# LEDBAKL_TPS61040DRV.net
KiCad netlist of a schematic drawn in Altium Designer
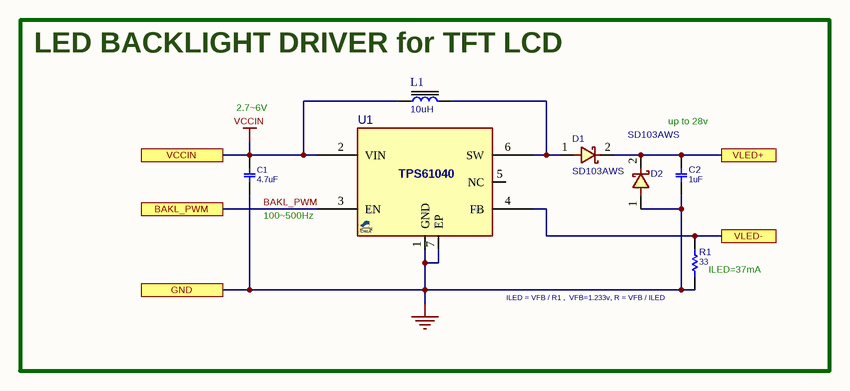
[diagram p0: LEDBAKL_TPS61040DRV.SchDoc]

(export (version "E")
  (design (tool "Eeschema 10.0.6"))
  (components
    (comp (ref "C1")
      (value "4.7uF")
      (footprint "C0402")
      (description "CAP, MLCC")
      (fields (field (name "MANF_P#") "CL05A475MP5NRNC") (field (name "MANF") "Samsung"))
      (libsource (lib "passive_smd") (part "CAP_SMD_MLCC"))
    )
    (comp (ref "C2")
      (value "1uF")
      (footprint "C0603")
      (description "CAP, MLCC")
      (fields (field (name "MANF_P#") "CL10A105KB8NNNC") (field (name "MANF") "Samsung"))
      (libsource (lib "passive_smd") (part "CAP_SMD_MLCC"))
    )
    (comp (ref "D1")
      (value "SD103AWS")
      (footprint "D_SOD323")
      (description "DIODE, SCHOTTKY, 40V, 2A")
      (fields (field (name "MANF") "DIODES"))
      (libsource (lib "diode") (part "DIODE_SMD_SCHOTTKY_1N5819"))
    )
    (comp (ref "D2")
      (value "SD103AWS")
      (footprint "D_SOD323")
      (description "DIODE, SCHOTTKY, 40V, 2A")
      (fields (field (name "MANF") "DIODES"))
      (libsource (lib "diode") (part "DIODE_SMD_SCHOTTKY_1N5819"))
    )
    (comp (ref "L1")
      (value "10uH")
      (footprint "L_4")
      (description "INDUCTOR, POWER, SMD")
      (fields (field (name "MANF_P#") "GCD43-100MC"))
      (libsource (lib "passive") (part "INDPWR_SMD"))
    )
    (comp (ref "R1")
      (value "33")
      (footprint "R0402")
      (description "RESISTOR, SMD, 20K, 0402")
      (fields (field (name "MANF") "Yageo") (field (name "MANF_P#") "RK73H1ETTP2002F"))
      (libsource (lib "chila_passive") (part "RES_SMD"))
    )
    (comp (ref "U1")
      (value "TPS61040")
      (footprint "SON65_6T_2020")
      (description "REG, Switching, Boost, 0.4A, ADJ, 1MHz, SOT-23-5")
      (fields (field (name "MANF_P#") "TPS61040DRV") (field (name "MANF") "TI"))
      (libsource (lib "pwr_switching_boost") (part "VREG_TPS61040_SON6"))
    )
  )
  (nets
    (net (code "1") (name "/BAKL_PWM") (class "Default")
      (node (ref "U1") (pin "3") (pinfunction "EN_3") (pintype "passive"))
    )
    (net (code "2") (name "/VLED+") (class "Default")
      (node (ref "C2") (pin "2") (pinfunction "2_2") (pintype "passive"))
      (node (ref "D1") (pin "2") (pinfunction "2_2") (pintype "passive"))
      (node (ref "D2") (pin "2") (pinfunction "2_2") (pintype "passive"))
    )
    (net (code "3") (name "/VLED-") (class "Default")
      (node (ref "R1") (pin "1") (pinfunction "1_1") (pintype "passive"))
      (node (ref "U1") (pin "4") (pinfunction "FB_4") (pintype "passive"))
    )
    (net (code "4") (name "GND") (class "Default")
      (node (ref "C1") (pin "1") (pinfunction "1_1") (pintype "passive"))
      (node (ref "C2") (pin "1") (pinfunction "1_1") (pintype "passive"))
      (node (ref "D2") (pin "1") (pinfunction "1_1") (pintype "passive"))
      (node (ref "R1") (pin "2") (pinfunction "2_2") (pintype "passive"))
      (node (ref "U1") (pin "1") (pinfunction "GND_1") (pintype "passive"))
      (node (ref "U1") (pin "7") (pinfunction "EP_7") (pintype "passive"))
    )
    (net (code "5") (name "Net-(U1-SW)") (class "Default")
      (node (ref "D1") (pin "1") (pinfunction "1_1") (pintype "passive"))
      (node (ref "L1") (pin "2") (pinfunction "2_2") (pintype "passive"))
      (node (ref "U1") (pin "6") (pinfunction "SW_6") (pintype "passive"))
    )
    (net (code "6") (name "VCCIN") (class "Default")
      (node (ref "C1") (pin "2") (pinfunction "2_2") (pintype "passive"))
      (node (ref "L1") (pin "1") (pinfunction "1_1") (pintype "passive"))
      (node (ref "U1") (pin "2") (pinfunction "VIN_2") (pintype "passive"))
    )
    (net (code "7") (name "unconnected-(U1-NC-Pad5)") (class "Default")
      (node (ref "U1") (pin "5") (pinfunction "NC_5") (pintype "passive"))
    )
  )
)
